# powerSupplyAndLED.net
KiCad netlist of a schematic drawn in EAGLE
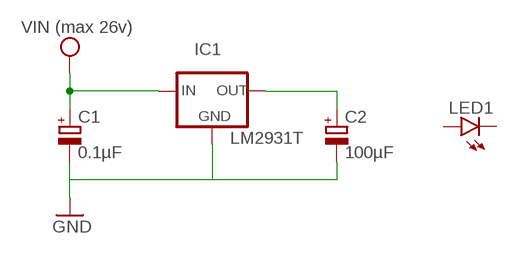
[diagram p0: schematic, sheet 1]

(export (version "E")
  (design (tool "Eeschema 10.0.6"))
  (components
    (comp (ref "C1")
      (value "0.1µF")
      (footprint "eagle-import:E5-5")
      (libsource (lib "eagle-import") (part "CPOL-EUE5-5"))
    )
    (comp (ref "C2")
      (value "100µF")
      (footprint "eagle-import:E5-5")
      (libsource (lib "eagle-import") (part "CPOL-EUE5-5"))
    )
    (comp (ref "IC1")
      (value "LM2931T")
      (footprint "eagle-import:TO220S")
      (libsource (lib "eagle-import") (part "LM2931T"))
    )
    (comp (ref "LED1")
      (value "LED5MM")
      (footprint "eagle-import:LED5MM")
      (libsource (lib "eagle-import") (part "LED5MM"))
    )
  )
  (nets
    (net (code "1") (name "GND") (class "Default")
      (node (ref "C1") (pin "-") (pinfunction "-_-") (pintype "passive"))
      (node (ref "C2") (pin "-") (pinfunction "-_-") (pintype "passive"))
      (node (ref "IC1") (pin "2") (pinfunction "GND_2") (pintype "input"))
    )
    (net (code "2") (name "Net-(IC1-OUT)") (class "Default")
      (node (ref "C2") (pin "+") (pinfunction "+_+") (pintype "passive"))
      (node (ref "IC1") (pin "3") (pinfunction "OUT_3") (pintype "passive"))
    )
    (net (code "3") (name "VIN (max 26v)") (class "Default")
      (node (ref "C1") (pin "+") (pinfunction "+_+") (pintype "passive"))
      (node (ref "IC1") (pin "1") (pinfunction "IN_1") (pintype "input"))
    )
    (net (code "4") (name "unconnected-(LED1-C-PadK)") (class "Default")
      (node (ref "LED1") (pin "K") (pinfunction "C_K") (pintype "passive"))
    )
    (net (code "5") (name "unconnected-(LED1-PadA)") (class "Default")
      (node (ref "LED1") (pin "A") (pinfunction "A_A") (pintype "passive"))
    )
  )
)
